# V2_0_1_Expansion_Card.net
KiCad netlist of a schematic drawn in EasyEDA Pro
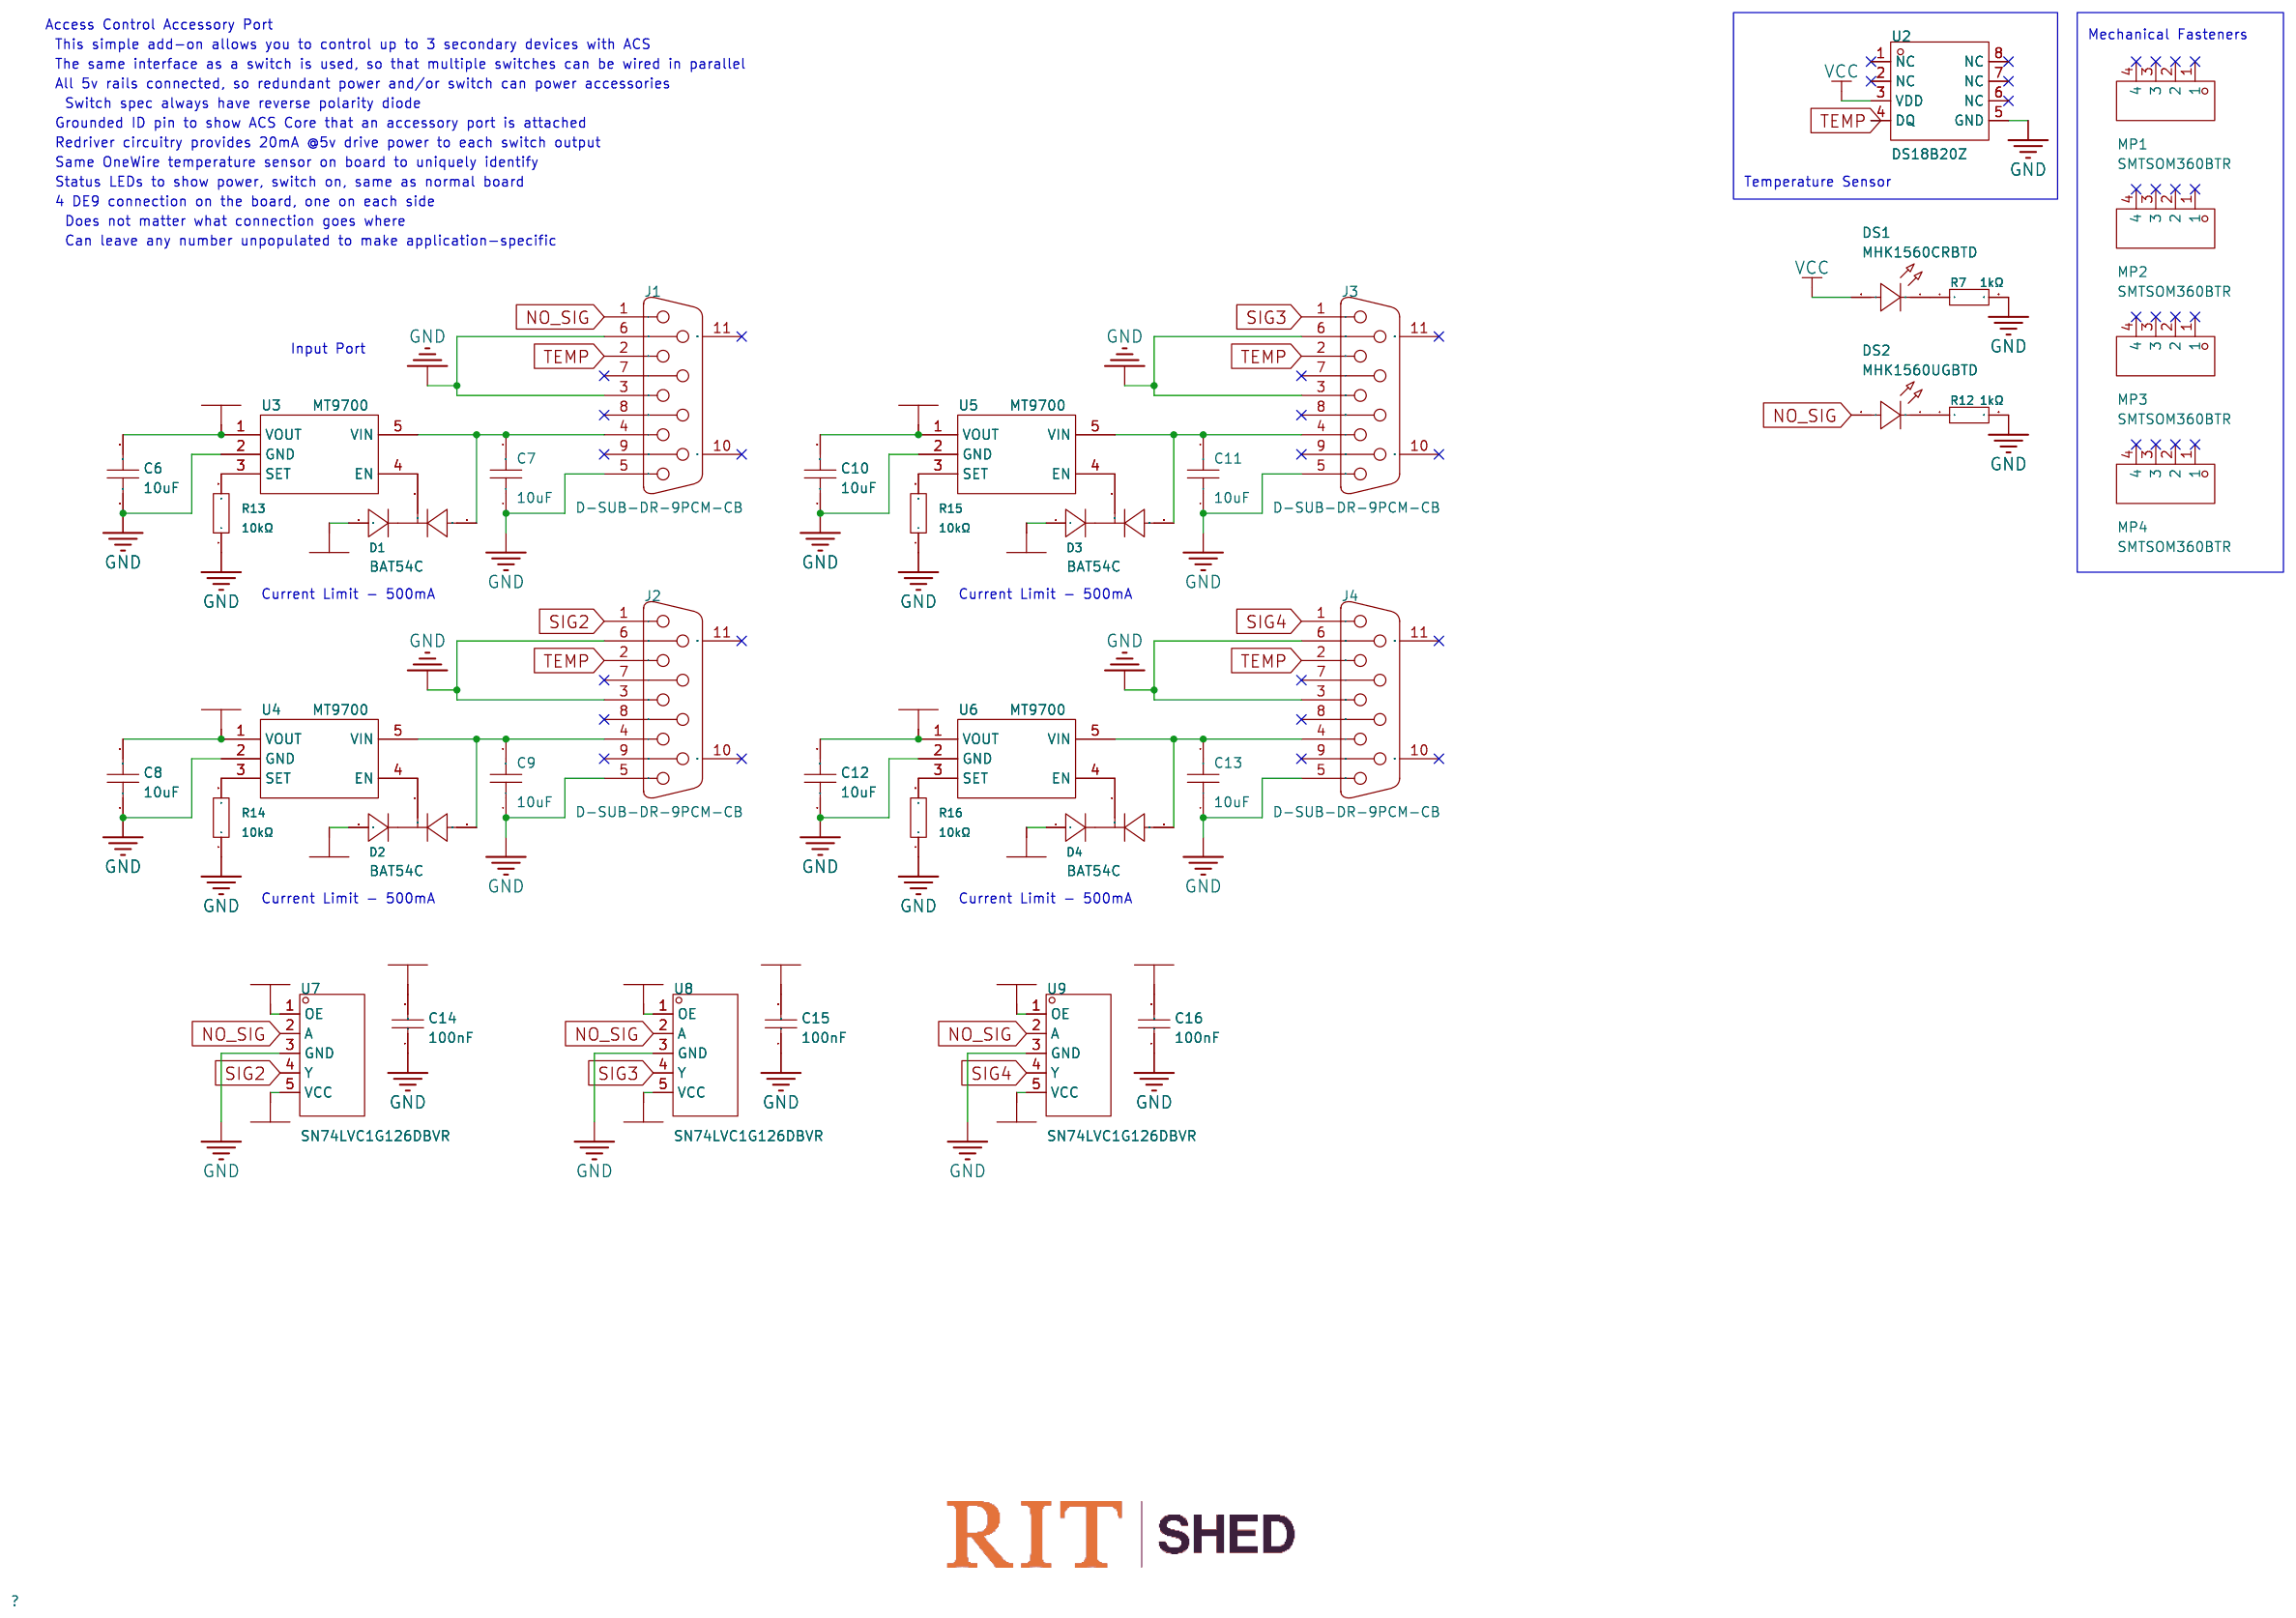
[diagram p0: schematic sheet]

(export (version "E")
  (design (tool "Eeschema 10.0.6"))
  (components
    (comp (ref "C6")
      (value "10uF")
      (footprint "easyedapro:C0603")
      (fields
        (field (name "Manufacturer Part") "CL10A106MA8NRNC")
        (field (name "Manufacturer") "SAMSUNG(三星)")
      )
      (libsource (lib "easyedapro") (part "CL10A106MA8NRNC"))
    )
    (comp (ref "C7")
      (value "10uF")
      (footprint "easyedapro:C0603")
      (fields
        (field (name "Manufacturer Part") "CL10A106MA8NRNC")
        (field (name "Manufacturer") "SAMSUNG(三星)")
      )
      (libsource (lib "easyedapro") (part "CL10A106MA8NRNC"))
    )
    (comp (ref "C8")
      (value "10uF")
      (footprint "easyedapro:C0603")
      (fields
        (field (name "Manufacturer Part") "CL10A106MA8NRNC")
        (field (name "Manufacturer") "SAMSUNG(三星)")
      )
      (libsource (lib "easyedapro") (part "CL10A106MA8NRNC"))
    )
    (comp (ref "C9")
      (value "10uF")
      (footprint "easyedapro:C0603")
      (fields
        (field (name "Manufacturer Part") "CL10A106MA8NRNC")
        (field (name "Manufacturer") "SAMSUNG(三星)")
      )
      (libsource (lib "easyedapro") (part "CL10A106MA8NRNC"))
    )
    (comp (ref "C10")
      (value "10uF")
      (footprint "easyedapro:C0603")
      (fields
        (field (name "Manufacturer Part") "CL10A106MA8NRNC")
        (field (name "Manufacturer") "SAMSUNG(三星)")
      )
      (libsource (lib "easyedapro") (part "CL10A106MA8NRNC"))
    )
    (comp (ref "C11")
      (value "10uF")
      (footprint "easyedapro:C0603")
      (fields
        (field (name "Manufacturer Part") "CL10A106MA8NRNC")
        (field (name "Manufacturer") "SAMSUNG(三星)")
      )
      (libsource (lib "easyedapro") (part "CL10A106MA8NRNC"))
    )
    (comp (ref "C12")
      (value "10uF")
      (footprint "easyedapro:C0603")
      (fields
        (field (name "Manufacturer Part") "CL10A106MA8NRNC")
        (field (name "Manufacturer") "SAMSUNG(三星)")
      )
      (libsource (lib "easyedapro") (part "CL10A106MA8NRNC"))
    )
    (comp (ref "C13")
      (value "10uF")
      (footprint "easyedapro:C0603")
      (fields
        (field (name "Manufacturer Part") "CL10A106MA8NRNC")
        (field (name "Manufacturer") "SAMSUNG(三星)")
      )
      (libsource (lib "easyedapro") (part "CL10A106MA8NRNC"))
    )
    (comp (ref "C14")
      (value "100nF")
      (footprint "easyedapro:C0603")
      (fields
        (field (name "Manufacturer Part") "CL10B104KA8NNNC")
        (field (name "Manufacturer") "SAMSUNG(三星)")
      )
      (libsource (lib "easyedapro") (part "CL10B104KA8NNNC"))
    )
    (comp (ref "C15")
      (value "100nF")
      (footprint "easyedapro:C0603")
      (fields
        (field (name "Manufacturer Part") "CL10B104KA8NNNC")
        (field (name "Manufacturer") "SAMSUNG(三星)")
      )
      (libsource (lib "easyedapro") (part "CL10B104KA8NNNC"))
    )
    (comp (ref "C16")
      (value "100nF")
      (footprint "easyedapro:C0603")
      (fields
        (field (name "Manufacturer Part") "CL10B104KA8NNNC")
        (field (name "Manufacturer") "SAMSUNG(三星)")
      )
      (libsource (lib "easyedapro") (part "CL10B104KA8NNNC"))
    )
    (comp (ref "D1")
      (value "BAT54C")
      (footprint "easyedapro:SOT-23-3_L2.9-W1.3-P1.90-LS2.4-BR")
      (fields (field (name "Manufacturer") "LGE(鲁光)"))
      (libsource (lib "easyedapro") (part "BAT54C_C2903788"))
    )
    (comp (ref "D2")
      (value "BAT54C")
      (footprint "easyedapro:SOT-23-3_L2.9-W1.3-P1.90-LS2.4-BR")
      (fields (field (name "Manufacturer") "LGE(鲁光)"))
      (libsource (lib "easyedapro") (part "BAT54C_C2903788"))
    )
    (comp (ref "D3")
      (value "BAT54C")
      (footprint "easyedapro:SOT-23-3_L2.9-W1.3-P1.90-LS2.4-BR")
      (fields (field (name "Manufacturer") "LGE(鲁光)"))
      (libsource (lib "easyedapro") (part "BAT54C_C2903788"))
    )
    (comp (ref "D4")
      (value "BAT54C")
      (footprint "easyedapro:SOT-23-3_L2.9-W1.3-P1.90-LS2.4-BR")
      (fields (field (name "Manufacturer") "LGE(鲁光)"))
      (libsource (lib "easyedapro") (part "BAT54C_C2903788"))
    )
    (comp (ref "DS1")
      (value "MHK1560CRBTD")
      (footprint "easyedapro:LED-TH_MHK1560UGBTD")
      (fields (field (name "Manufacturer") "MEIHUA(美华)"))
      (libsource (lib "easyedapro") (part "MHK1560CGBTD"))
    )
    (comp (ref "DS2")
      (value "MHK1560UGBTD")
      (footprint "easyedapro:LED-TH_MHK1560UGBTD")
      (fields (field (name "Manufacturer") "MEIHUA(美华)"))
      (libsource (lib "easyedapro") (part "MHK1560UGBTD"))
    )
    (comp (ref "J1")
      (value "D-SUB-DR-9PCM-CB")
      (footprint "easyedapro:DB9-TH_ID09S33E4GV00LF")
      (fields (field (name "Manufacturer") "XUNPU(讯普)"))
      (libsource (lib "easyedapro") (part "D-SUB-DR-9PCM-CB"))
    )
    (comp (ref "J2")
      (value "D-SUB-DR-9PCM-CB")
      (footprint "easyedapro:DB9-TH_ID09S33E4GV00LF")
      (fields (field (name "Manufacturer") "XUNPU(讯普)"))
      (libsource (lib "easyedapro") (part "D-SUB-DR-9PCM-CB"))
    )
    (comp (ref "J3")
      (value "D-SUB-DR-9PCM-CB")
      (footprint "easyedapro:DB9-TH_ID09S33E4GV00LF")
      (fields (field (name "Manufacturer") "XUNPU(讯普)"))
      (libsource (lib "easyedapro") (part "D-SUB-DR-9PCM-CB"))
    )
    (comp (ref "J4")
      (value "D-SUB-DR-9PCM-CB")
      (footprint "easyedapro:DB9-TH_ID09S33E4GV00LF")
      (fields (field (name "Manufacturer") "XUNPU(讯普)"))
      (libsource (lib "easyedapro") (part "D-SUB-DR-9PCM-CB"))
    )
    (comp (ref "MP1")
      (value "SMTSOM360BTR")
      (footprint "easyedapro:SMD_BD5.6-D4.1")
      (fields (field (name "Manufacturer") "YIYUAN(怡远)"))
      (libsource (lib "easyedapro") (part "SMTSOM360BTR"))
    )
    (comp (ref "MP2")
      (value "SMTSOM360BTR")
      (footprint "easyedapro:SMD_BD5.6-D4.1")
      (fields (field (name "Manufacturer") "YIYUAN(怡远)"))
      (libsource (lib "easyedapro") (part "SMTSOM360BTR"))
    )
    (comp (ref "MP3")
      (value "SMTSOM360BTR")
      (footprint "easyedapro:SMD_BD5.6-D4.1")
      (fields (field (name "Manufacturer") "YIYUAN(怡远)"))
      (libsource (lib "easyedapro") (part "SMTSOM360BTR"))
    )
    (comp (ref "MP4")
      (value "SMTSOM360BTR")
      (footprint "easyedapro:SMD_BD5.6-D4.1")
      (fields (field (name "Manufacturer") "YIYUAN(怡远)"))
      (libsource (lib "easyedapro") (part "SMTSOM360BTR"))
    )
    (comp (ref "R7")
      (value "1kΩ")
      (footprint "easyedapro:R0603")
      (fields
        (field (name "Manufacturer Part") "0603WAF1001T5E")
        (field (name "Manufacturer") "UNI-ROYAL(厚声)")
      )
      (libsource (lib "easyedapro") (part "0603WAF1001T5E"))
    )
    (comp (ref "R12")
      (value "1kΩ")
      (footprint "easyedapro:R0603")
      (fields
        (field (name "Manufacturer Part") "0603WAF1001T5E")
        (field (name "Manufacturer") "UNI-ROYAL(厚声)")
      )
      (libsource (lib "easyedapro") (part "0603WAF1001T5E"))
    )
    (comp (ref "R13")
      (value "10kΩ")
      (footprint "easyedapro:R0603")
      (fields
        (field (name "Manufacturer Part") "0603WAF1002T5E")
        (field (name "Manufacturer") "UNI-ROYAL(厚声)")
      )
      (libsource (lib "easyedapro") (part "0603WAF1002T5E"))
    )
    (comp (ref "R14")
      (value "10kΩ")
      (footprint "easyedapro:R0603")
      (fields
        (field (name "Manufacturer Part") "0603WAF1002T5E")
        (field (name "Manufacturer") "UNI-ROYAL(厚声)")
      )
      (libsource (lib "easyedapro") (part "0603WAF1002T5E"))
    )
    (comp (ref "R15")
      (value "10kΩ")
      (footprint "easyedapro:R0603")
      (fields
        (field (name "Manufacturer Part") "0603WAF1002T5E")
        (field (name "Manufacturer") "UNI-ROYAL(厚声)")
      )
      (libsource (lib "easyedapro") (part "0603WAF1002T5E"))
    )
    (comp (ref "R16")
      (value "10kΩ")
      (footprint "easyedapro:R0603")
      (fields
        (field (name "Manufacturer Part") "0603WAF1002T5E")
        (field (name "Manufacturer") "UNI-ROYAL(厚声)")
      )
      (libsource (lib "easyedapro") (part "0603WAF1002T5E"))
    )
    (comp (ref "U2")
      (value "DS18B20Z")
      (footprint "easyedapro:SOP-8_L4.9-W3.9-P1.27-LS6.0-BL")
      (description "Resolution:±0.4°C Resolution:±0.4°C Supply Voltage:2.5V~5.5V Supply Voltage:2.5V~5.5V")
      (fields (field (name "Manufacturer") "UMW(友台半导体)"))
      (libsource (lib "easyedapro") (part "DS18B20Z"))
    )
    (comp (ref "U3")
      (value "MT9700")
      (footprint "easyedapro:SOT-23-5_L3.0-W1.7-P0.95-LS2.8-BR")
      (fields (field (name "Manufacturer") "西安航天民芯"))
      (libsource (lib "easyedapro") (part "MT9700"))
    )
    (comp (ref "U4")
      (value "MT9700")
      (footprint "easyedapro:SOT-23-5_L3.0-W1.7-P0.95-LS2.8-BR")
      (fields (field (name "Manufacturer") "西安航天民芯"))
      (libsource (lib "easyedapro") (part "MT9700"))
    )
    (comp (ref "U5")
      (value "MT9700")
      (footprint "easyedapro:SOT-23-5_L3.0-W1.7-P0.95-LS2.8-BR")
      (fields (field (name "Manufacturer") "西安航天民芯"))
      (libsource (lib "easyedapro") (part "MT9700"))
    )
    (comp (ref "U6")
      (value "MT9700")
      (footprint "easyedapro:SOT-23-5_L3.0-W1.7-P0.95-LS2.8-BR")
      (fields (field (name "Manufacturer") "西安航天民芯"))
      (libsource (lib "easyedapro") (part "MT9700"))
    )
    (comp (ref "U7")
      (value "SN74LVC1G126DBVR")
      (footprint "easyedapro:SOT-23-5_L3.0-W1.7-P0.95-LS2.8-BR")
      (fields (field (name "Manufacturer") "TI(德州仪器)"))
      (libsource (lib "easyedapro") (part "SN74LVC1G126DBVR"))
    )
    (comp (ref "U8")
      (value "SN74LVC1G126DBVR")
      (footprint "easyedapro:SOT-23-5_L3.0-W1.7-P0.95-LS2.8-BR")
      (fields (field (name "Manufacturer") "TI(德州仪器)"))
      (libsource (lib "easyedapro") (part "SN74LVC1G126DBVR"))
    )
    (comp (ref "U9")
      (value "SN74LVC1G126DBVR")
      (footprint "easyedapro:SOT-23-5_L3.0-W1.7-P0.95-LS2.8-BR")
      (fields (field (name "Manufacturer") "TI(德州仪器)"))
      (libsource (lib "easyedapro") (part "SN74LVC1G126DBVR"))
    )
  )
  (nets
    (net (code "1") (name "GND") (class "Default")
      (node (ref "C10") (pin "1") (pinfunction "1_1") (pintype "input"))
      (node (ref "C11") (pin "1") (pinfunction "1_1") (pintype "input"))
      (node (ref "C12") (pin "1") (pinfunction "1_1") (pintype "input"))
      (node (ref "C13") (pin "1") (pinfunction "1_1") (pintype "input"))
      (node (ref "C14") (pin "1") (pinfunction "1_1") (pintype "input"))
      (node (ref "C15") (pin "1") (pinfunction "1_1") (pintype "input"))
      (node (ref "C16") (pin "1") (pinfunction "1_1") (pintype "input"))
      (node (ref "C6") (pin "1") (pinfunction "1_1") (pintype "input"))
      (node (ref "C7") (pin "1") (pinfunction "1_1") (pintype "input"))
      (node (ref "C8") (pin "1") (pinfunction "1_1") (pintype "input"))
      (node (ref "C9") (pin "1") (pinfunction "1_1") (pintype "input"))
      (node (ref "J1") (pin "3") (pinfunction "3_3") (pintype "input"))
      (node (ref "J1") (pin "5") (pinfunction "5_5") (pintype "input"))
      (node (ref "J1") (pin "6") (pinfunction "6_6") (pintype "input"))
      (node (ref "J2") (pin "3") (pinfunction "3_3") (pintype "input"))
      (node (ref "J2") (pin "5") (pinfunction "5_5") (pintype "input"))
      (node (ref "J2") (pin "6") (pinfunction "6_6") (pintype "input"))
      (node (ref "J3") (pin "3") (pinfunction "3_3") (pintype "input"))
      (node (ref "J3") (pin "5") (pinfunction "5_5") (pintype "input"))
      (node (ref "J3") (pin "6") (pinfunction "6_6") (pintype "input"))
      (node (ref "J4") (pin "3") (pinfunction "3_3") (pintype "input"))
      (node (ref "J4") (pin "5") (pinfunction "5_5") (pintype "input"))
      (node (ref "J4") (pin "6") (pinfunction "6_6") (pintype "input"))
      (node (ref "R12") (pin "2") (pinfunction "2_2") (pintype "input"))
      (node (ref "R13") (pin "1") (pinfunction "1_1") (pintype "input"))
      (node (ref "R14") (pin "1") (pinfunction "1_1") (pintype "input"))
      (node (ref "R15") (pin "1") (pinfunction "1_1") (pintype "input"))
      (node (ref "R16") (pin "1") (pinfunction "1_1") (pintype "input"))
      (node (ref "R7") (pin "2") (pinfunction "2_2") (pintype "input"))
      (node (ref "U2") (pin "5") (pinfunction "GND_5") (pintype "unspecified"))
      (node (ref "U3") (pin "2") (pinfunction "GND_2") (pintype "input"))
      (node (ref "U4") (pin "2") (pinfunction "GND_2") (pintype "input"))
      (node (ref "U5") (pin "2") (pinfunction "GND_2") (pintype "input"))
      (node (ref "U6") (pin "2") (pinfunction "GND_2") (pintype "input"))
      (node (ref "U7") (pin "3") (pinfunction "GND_3") (pintype "input"))
      (node (ref "U8") (pin "3") (pinfunction "GND_3") (pintype "input"))
      (node (ref "U9") (pin "3") (pinfunction "GND_3") (pintype "input"))
    )
    (net (code "2") (name "NO_SIG") (class "Default")
      (node (ref "DS2") (pin "2") (pinfunction "A_2") (pintype "unspecified"))
      (node (ref "J1") (pin "1") (pinfunction "1_1") (pintype "input"))
      (node (ref "U7") (pin "2") (pinfunction "A_2") (pintype "input"))
      (node (ref "U8") (pin "2") (pinfunction "A_2") (pintype "input"))
      (node (ref "U9") (pin "2") (pinfunction "A_2") (pintype "input"))
    )
    (net (code "3") (name "Net-(DS1-K)") (class "Default")
      (node (ref "DS1") (pin "1") (pinfunction "K_1") (pintype "unspecified"))
      (node (ref "R7") (pin "1") (pinfunction "1_1") (pintype "input"))
    )
    (net (code "4") (name "Net-(DS2-K)") (class "Default")
      (node (ref "DS2") (pin "1") (pinfunction "K_1") (pintype "unspecified"))
      (node (ref "R12") (pin "1") (pinfunction "1_1") (pintype "input"))
    )
    (net (code "5") (name "Net-(U3-EN)") (class "Default")
      (node (ref "D1") (pin "3") (pinfunction "3_3") (pintype "input"))
      (node (ref "U3") (pin "4") (pinfunction "EN_4") (pintype "input"))
    )
    (net (code "6") (name "Net-(U3-SET)") (class "Default")
      (node (ref "R13") (pin "2") (pinfunction "2_2") (pintype "input"))
      (node (ref "U3") (pin "3") (pinfunction "SET_3") (pintype "input"))
    )
    (net (code "7") (name "Net-(U3-VIN)") (class "Default")
      (node (ref "C7") (pin "2") (pinfunction "2_2") (pintype "input"))
      (node (ref "D1") (pin "2") (pinfunction "2_2") (pintype "input"))
      (node (ref "J1") (pin "4") (pinfunction "4_4") (pintype "input"))
      (node (ref "U3") (pin "5") (pinfunction "VIN_5") (pintype "input"))
    )
    (net (code "8") (name "Net-(U4-EN)") (class "Default")
      (node (ref "D2") (pin "3") (pinfunction "3_3") (pintype "input"))
      (node (ref "U4") (pin "4") (pinfunction "EN_4") (pintype "input"))
    )
    (net (code "9") (name "Net-(U4-SET)") (class "Default")
      (node (ref "R14") (pin "2") (pinfunction "2_2") (pintype "input"))
      (node (ref "U4") (pin "3") (pinfunction "SET_3") (pintype "input"))
    )
    (net (code "10") (name "Net-(U4-VIN)") (class "Default")
      (node (ref "C9") (pin "2") (pinfunction "2_2") (pintype "input"))
      (node (ref "D2") (pin "2") (pinfunction "2_2") (pintype "input"))
      (node (ref "J2") (pin "4") (pinfunction "4_4") (pintype "input"))
      (node (ref "U4") (pin "5") (pinfunction "VIN_5") (pintype "input"))
    )
    (net (code "11") (name "Net-(U5-EN)") (class "Default")
      (node (ref "D3") (pin "3") (pinfunction "3_3") (pintype "input"))
      (node (ref "U5") (pin "4") (pinfunction "EN_4") (pintype "input"))
    )
    (net (code "12") (name "Net-(U5-SET)") (class "Default")
      (node (ref "R15") (pin "2") (pinfunction "2_2") (pintype "input"))
      (node (ref "U5") (pin "3") (pinfunction "SET_3") (pintype "input"))
    )
    (net (code "13") (name "Net-(U5-VIN)") (class "Default")
      (node (ref "C11") (pin "2") (pinfunction "2_2") (pintype "input"))
      (node (ref "D3") (pin "2") (pinfunction "2_2") (pintype "input"))
      (node (ref "J3") (pin "4") (pinfunction "4_4") (pintype "input"))
      (node (ref "U5") (pin "5") (pinfunction "VIN_5") (pintype "input"))
    )
    (net (code "14") (name "Net-(U6-EN)") (class "Default")
      (node (ref "D4") (pin "3") (pinfunction "3_3") (pintype "input"))
      (node (ref "U6") (pin "4") (pinfunction "EN_4") (pintype "input"))
    )
    (net (code "15") (name "Net-(U6-SET)") (class "Default")
      (node (ref "R16") (pin "2") (pinfunction "2_2") (pintype "input"))
      (node (ref "U6") (pin "3") (pinfunction "SET_3") (pintype "input"))
    )
    (net (code "16") (name "Net-(U6-VIN)") (class "Default")
      (node (ref "C13") (pin "2") (pinfunction "2_2") (pintype "input"))
      (node (ref "D4") (pin "2") (pinfunction "2_2") (pintype "input"))
      (node (ref "J4") (pin "4") (pinfunction "4_4") (pintype "input"))
      (node (ref "U6") (pin "5") (pinfunction "VIN_5") (pintype "input"))
    )
    (net (code "17") (name "SIG2") (class "Default")
      (node (ref "J2") (pin "1") (pinfunction "1_1") (pintype "input"))
      (node (ref "U7") (pin "4") (pinfunction "Y_4") (pintype "input"))
    )
    (net (code "18") (name "SIG3") (class "Default")
      (node (ref "J3") (pin "1") (pinfunction "1_1") (pintype "input"))
      (node (ref "U8") (pin "4") (pinfunction "Y_4") (pintype "input"))
    )
    (net (code "19") (name "SIG4") (class "Default")
      (node (ref "J4") (pin "1") (pinfunction "1_1") (pintype "input"))
      (node (ref "U9") (pin "4") (pinfunction "Y_4") (pintype "input"))
    )
    (net (code "20") (name "TEMP") (class "Default")
      (node (ref "J1") (pin "2") (pinfunction "2_2") (pintype "input"))
      (node (ref "J2") (pin "2") (pinfunction "2_2") (pintype "input"))
      (node (ref "J3") (pin "2") (pinfunction "2_2") (pintype "input"))
      (node (ref "J4") (pin "2") (pinfunction "2_2") (pintype "input"))
      (node (ref "U2") (pin "4") (pinfunction "DQ_4") (pintype "unspecified"))
    )
    (net (code "21") (name "VCC") (class "Default")
      (node (ref "C10") (pin "2") (pinfunction "2_2") (pintype "input"))
      (node (ref "C12") (pin "2") (pinfunction "2_2") (pintype "input"))
      (node (ref "C14") (pin "2") (pinfunction "2_2") (pintype "input"))
      (node (ref "C15") (pin "2") (pinfunction "2_2") (pintype "input"))
      (node (ref "C16") (pin "2") (pinfunction "2_2") (pintype "input"))
      (node (ref "C6") (pin "2") (pinfunction "2_2") (pintype "input"))
      (node (ref "C8") (pin "2") (pinfunction "2_2") (pintype "input"))
      (node (ref "D1") (pin "1") (pinfunction "1_1") (pintype "input"))
      (node (ref "D2") (pin "1") (pinfunction "1_1") (pintype "input"))
      (node (ref "D3") (pin "1") (pinfunction "1_1") (pintype "input"))
      (node (ref "D4") (pin "1") (pinfunction "1_1") (pintype "input"))
      (node (ref "DS1") (pin "2") (pinfunction "A_2") (pintype "unspecified"))
      (node (ref "U2") (pin "3") (pinfunction "VDD_3") (pintype "unspecified"))
      (node (ref "U3") (pin "1") (pinfunction "VOUT_1") (pintype "input"))
      (node (ref "U4") (pin "1") (pinfunction "VOUT_1") (pintype "input"))
      (node (ref "U5") (pin "1") (pinfunction "VOUT_1") (pintype "input"))
      (node (ref "U6") (pin "1") (pinfunction "VOUT_1") (pintype "input"))
      (node (ref "U7") (pin "1") (pinfunction "OE_1") (pintype "input"))
      (node (ref "U7") (pin "5") (pinfunction "VCC_5") (pintype "input"))
      (node (ref "U8") (pin "1") (pinfunction "OE_1") (pintype "input"))
      (node (ref "U8") (pin "5") (pinfunction "VCC_5") (pintype "input"))
      (node (ref "U9") (pin "1") (pinfunction "OE_1") (pintype "input"))
      (node (ref "U9") (pin "5") (pinfunction "VCC_5") (pintype "input"))
    )
    (net (code "22") (name "unconnected-(J1-MH1-Pad10)") (class "Default")
      (node (ref "J1") (pin "10") (pinfunction "MH1_10") (pintype "input+no_connect"))
    )
    (net (code "23") (name "unconnected-(J1-MH2-Pad11)") (class "Default")
      (node (ref "J1") (pin "11") (pinfunction "MH2_11") (pintype "input+no_connect"))
    )
    (net (code "24") (name "unconnected-(J1-Pad7)") (class "Default")
      (node (ref "J1") (pin "7") (pinfunction "7_7") (pintype "input+no_connect"))
    )
    (net (code "25") (name "unconnected-(J1-Pad8)") (class "Default")
      (node (ref "J1") (pin "8") (pinfunction "8_8") (pintype "input+no_connect"))
    )
    (net (code "26") (name "unconnected-(J1-Pad9)") (class "Default")
      (node (ref "J1") (pin "9") (pinfunction "9_9") (pintype "input+no_connect"))
    )
    (net (code "27") (name "unconnected-(J2-MH1-Pad10)") (class "Default")
      (node (ref "J2") (pin "10") (pinfunction "MH1_10") (pintype "input+no_connect"))
    )
    (net (code "28") (name "unconnected-(J2-MH2-Pad11)") (class "Default")
      (node (ref "J2") (pin "11") (pinfunction "MH2_11") (pintype "input+no_connect"))
    )
    (net (code "29") (name "unconnected-(J2-Pad7)") (class "Default")
      (node (ref "J2") (pin "7") (pinfunction "7_7") (pintype "input+no_connect"))
    )
    (net (code "30") (name "unconnected-(J2-Pad8)") (class "Default")
      (node (ref "J2") (pin "8") (pinfunction "8_8") (pintype "input+no_connect"))
    )
    (net (code "31") (name "unconnected-(J2-Pad9)") (class "Default")
      (node (ref "J2") (pin "9") (pinfunction "9_9") (pintype "input+no_connect"))
    )
    (net (code "32") (name "unconnected-(J3-MH1-Pad10)") (class "Default")
      (node (ref "J3") (pin "10") (pinfunction "MH1_10") (pintype "input+no_connect"))
    )
    (net (code "33") (name "unconnected-(J3-MH2-Pad11)") (class "Default")
      (node (ref "J3") (pin "11") (pinfunction "MH2_11") (pintype "input+no_connect"))
    )
    (net (code "34") (name "unconnected-(J3-Pad7)") (class "Default")
      (node (ref "J3") (pin "7") (pinfunction "7_7") (pintype "input+no_connect"))
    )
    (net (code "35") (name "unconnected-(J3-Pad8)") (class "Default")
      (node (ref "J3") (pin "8") (pinfunction "8_8") (pintype "input+no_connect"))
    )
    (net (code "36") (name "unconnected-(J3-Pad9)") (class "Default")
      (node (ref "J3") (pin "9") (pinfunction "9_9") (pintype "input+no_connect"))
    )
    (net (code "37") (name "unconnected-(J4-MH1-Pad10)") (class "Default")
      (node (ref "J4") (pin "10") (pinfunction "MH1_10") (pintype "input+no_connect"))
    )
    (net (code "38") (name "unconnected-(J4-MH2-Pad11)") (class "Default")
      (node (ref "J4") (pin "11") (pinfunction "MH2_11") (pintype "input+no_connect"))
    )
    (net (code "39") (name "unconnected-(J4-Pad7)") (class "Default")
      (node (ref "J4") (pin "7") (pinfunction "7_7") (pintype "input+no_connect"))
    )
    (net (code "40") (name "unconnected-(J4-Pad8)") (class "Default")
      (node (ref "J4") (pin "8") (pinfunction "8_8") (pintype "input+no_connect"))
    )
    (net (code "41") (name "unconnected-(J4-Pad9)") (class "Default")
      (node (ref "J4") (pin "9") (pinfunction "9_9") (pintype "input+no_connect"))
    )
    (net (code "42") (name "unconnected-(MP1-Pad1)") (class "Default")
      (node (ref "MP1") (pin "1") (pinfunction "1_1") (pintype "unspecified+no_connect"))
    )
    (net (code "43") (name "unconnected-(MP1-Pad2)") (class "Default")
      (node (ref "MP1") (pin "2") (pinfunction "2_2") (pintype "unspecified+no_connect"))
    )
    (net (code "44") (name "unconnected-(MP1-Pad3)") (class "Default")
      (node (ref "MP1") (pin "3") (pinfunction "3_3") (pintype "unspecified+no_connect"))
    )
    (net (code "45") (name "unconnected-(MP1-Pad4)") (class "Default")
      (node (ref "MP1") (pin "4") (pinfunction "4_4") (pintype "unspecified+no_connect"))
    )
    (net (code "46") (name "unconnected-(MP2-Pad1)") (class "Default")
      (node (ref "MP2") (pin "1") (pinfunction "1_1") (pintype "unspecified+no_connect"))
    )
    (net (code "47") (name "unconnected-(MP2-Pad2)") (class "Default")
      (node (ref "MP2") (pin "2") (pinfunction "2_2") (pintype "unspecified+no_connect"))
    )
    (net (code "48") (name "unconnected-(MP2-Pad3)") (class "Default")
      (node (ref "MP2") (pin "3") (pinfunction "3_3") (pintype "unspecified+no_connect"))
    )
    (net (code "49") (name "unconnected-(MP2-Pad4)") (class "Default")
      (node (ref "MP2") (pin "4") (pinfunction "4_4") (pintype "unspecified+no_connect"))
    )
    (net (code "50") (name "unconnected-(MP3-Pad1)") (class "Default")
      (node (ref "MP3") (pin "1") (pinfunction "1_1") (pintype "unspecified+no_connect"))
    )
    (net (code "51") (name "unconnected-(MP3-Pad2)") (class "Default")
      (node (ref "MP3") (pin "2") (pinfunction "2_2") (pintype "unspecified+no_connect"))
    )
    (net (code "52") (name "unconnected-(MP3-Pad3)") (class "Default")
      (node (ref "MP3") (pin "3") (pinfunction "3_3") (pintype "unspecified+no_connect"))
    )
    (net (code "53") (name "unconnected-(MP3-Pad4)") (class "Default")
      (node (ref "MP3") (pin "4") (pinfunction "4_4") (pintype "unspecified+no_connect"))
    )
    (net (code "54") (name "unconnected-(MP4-Pad1)") (class "Default")
      (node (ref "MP4") (pin "1") (pinfunction "1_1") (pintype "unspecified+no_connect"))
    )
    (net (code "55") (name "unconnected-(MP4-Pad2)") (class "Default")
      (node (ref "MP4") (pin "2") (pinfunction "2_2") (pintype "unspecified+no_connect"))
    )
    (net (code "56") (name "unconnected-(MP4-Pad3)") (class "Default")
      (node (ref "MP4") (pin "3") (pinfunction "3_3") (pintype "unspecified+no_connect"))
    )
    (net (code "57") (name "unconnected-(MP4-Pad4)") (class "Default")
      (node (ref "MP4") (pin "4") (pinfunction "4_4") (pintype "unspecified+no_connect"))
    )
    (net (code "58") (name "unconnected-(U2-NC-Pad1)") (class "Default")
      (node (ref "U2") (pin "1") (pinfunction "NC_1") (pintype "unspecified+no_connect"))
    )
    (net (code "59") (name "unconnected-(U2-NC-Pad2)") (class "Default")
      (node (ref "U2") (pin "2") (pinfunction "NC_2") (pintype "unspecified+no_connect"))
    )
    (net (code "60") (name "unconnected-(U2-NC-Pad6)") (class "Default")
      (node (ref "U2") (pin "6") (pinfunction "NC_6") (pintype "unspecified+no_connect"))
    )
    (net (code "61") (name "unconnected-(U2-NC-Pad7)") (class "Default")
      (node (ref "U2") (pin "7") (pinfunction "NC_7") (pintype "unspecified+no_connect"))
    )
    (net (code "62") (name "unconnected-(U2-NC-Pad8)") (class "Default")
      (node (ref "U2") (pin "8") (pinfunction "NC_8") (pintype "unspecified+no_connect"))
    )
  )
)
